# FPGA_POWER.net
KiCad netlist of a schematic drawn in Altium Designer
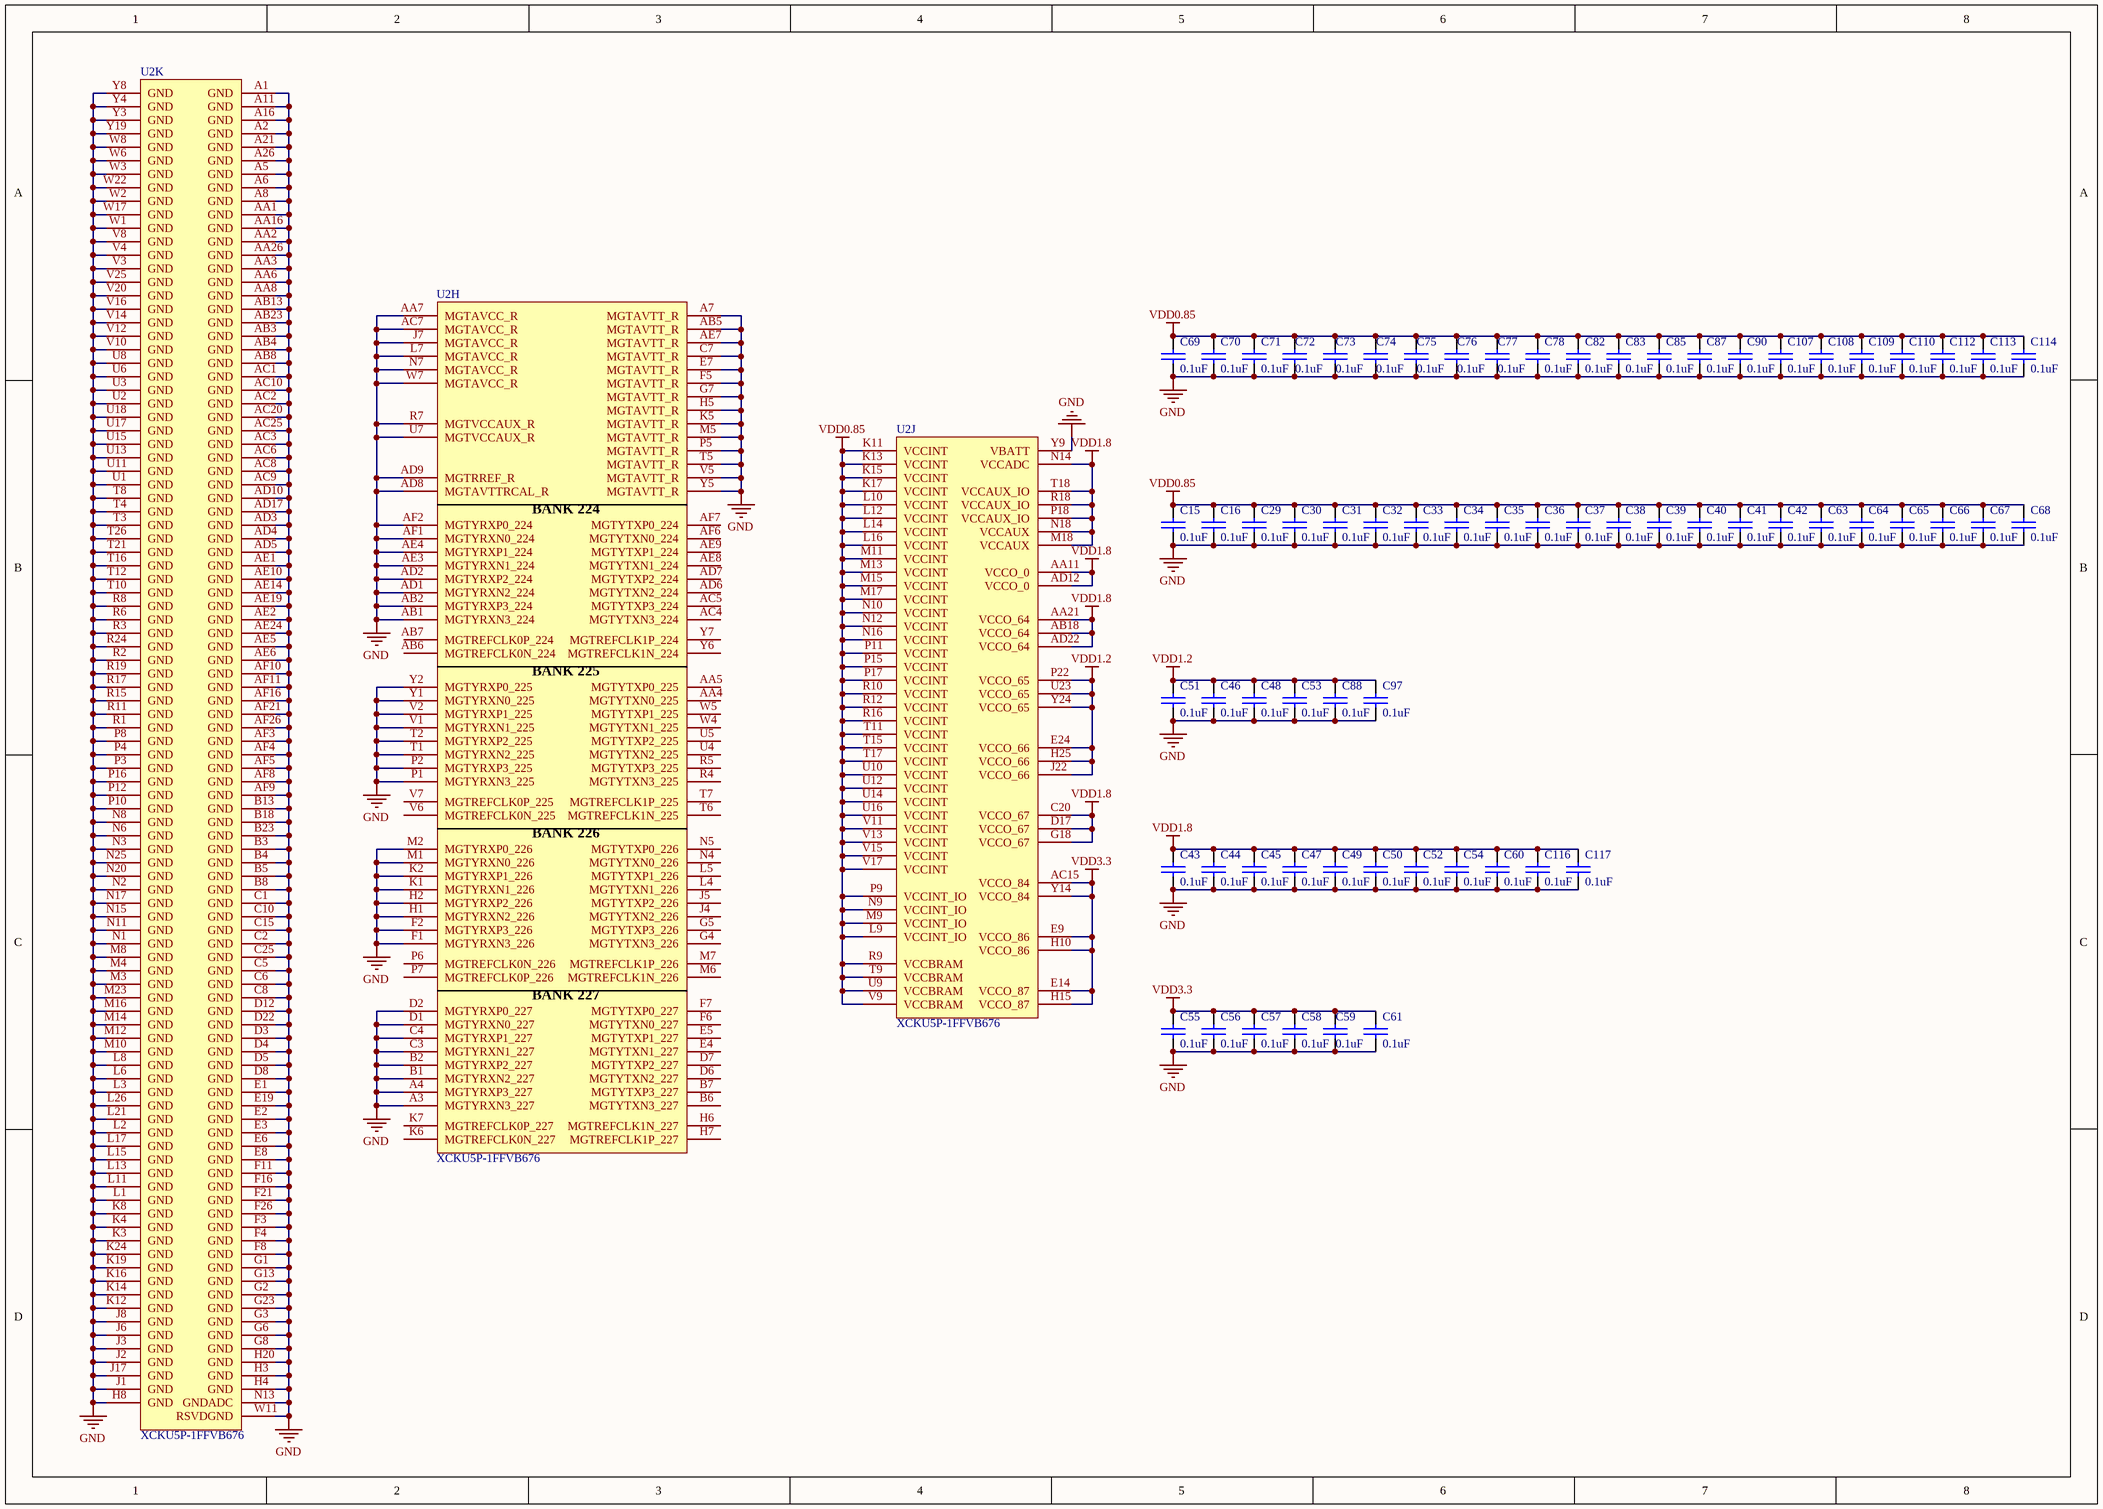
[diagram p0: FPGA POWER.SchDoc]

(export (version "E")
  (design (tool "Eeschema 10.0.6"))
  (components
    (comp (ref "C15") (value "0.1uF") (footprint "0402_C_M") (libsource (lib "Component") (part "CAP")))
    (comp (ref "C16") (value "0.1uF") (footprint "0402_C_M") (libsource (lib "Component") (part "CAP")))
    (comp (ref "C29") (value "0.1uF") (footprint "0402_C_M") (libsource (lib "Component") (part "CAP")))
    (comp (ref "C30") (value "0.1uF") (footprint "0402_C_M") (libsource (lib "Component") (part "CAP")))
    (comp (ref "C31") (value "0.1uF") (footprint "0402_C_M") (libsource (lib "Component") (part "CAP")))
    (comp (ref "C32") (value "0.1uF") (footprint "0402_C_M") (libsource (lib "Component") (part "CAP")))
    (comp (ref "C33") (value "0.1uF") (footprint "0402_C_M") (libsource (lib "Component") (part "CAP")))
    (comp (ref "C34") (value "0.1uF") (footprint "0402_C_M") (libsource (lib "Component") (part "CAP")))
    (comp (ref "C35") (value "0.1uF") (footprint "0402_C_M") (libsource (lib "Component") (part "CAP")))
    (comp (ref "C36") (value "0.1uF") (footprint "0402_C_M") (libsource (lib "Component") (part "CAP")))
    (comp (ref "C37") (value "0.1uF") (footprint "0402_C_M") (libsource (lib "Component") (part "CAP")))
    (comp (ref "C38") (value "0.1uF") (footprint "0402_C_M") (libsource (lib "Component") (part "CAP")))
    (comp (ref "C39") (value "0.1uF") (footprint "0402_C_M") (libsource (lib "Component") (part "CAP")))
    (comp (ref "C40") (value "0.1uF") (footprint "0402_C_M") (libsource (lib "Component") (part "CAP")))
    (comp (ref "C41") (value "0.1uF") (footprint "0402_C_M") (libsource (lib "Component") (part "CAP")))
    (comp (ref "C42") (value "0.1uF") (footprint "0402_C_M") (libsource (lib "Component") (part "CAP")))
    (comp (ref "C43") (value "0.1uF") (footprint "0402_C_M") (libsource (lib "Component") (part "CAP")))
    (comp (ref "C44") (value "0.1uF") (footprint "0402_C_M") (libsource (lib "Component") (part "CAP")))
    (comp (ref "C45") (value "0.1uF") (footprint "0402_C_M") (libsource (lib "Component") (part "CAP")))
    (comp (ref "C46") (value "0.1uF") (footprint "0402_C_M") (libsource (lib "Component") (part "CAP")))
    (comp (ref "C47") (value "0.1uF") (footprint "0402_C_M") (libsource (lib "Component") (part "CAP")))
    (comp (ref "C48") (value "0.1uF") (footprint "0402_C_M") (libsource (lib "Component") (part "CAP")))
    (comp (ref "C49") (value "0.1uF") (footprint "0402_C_M") (libsource (lib "Component") (part "CAP")))
    (comp (ref "C50") (value "0.1uF") (footprint "0402_C_M") (libsource (lib "Component") (part "CAP")))
    (comp (ref "C51") (value "0.1uF") (footprint "0402_C_M") (libsource (lib "Component") (part "CAP")))
    (comp (ref "C52") (value "0.1uF") (footprint "0402_C_M") (libsource (lib "Component") (part "CAP")))
    (comp (ref "C53") (value "0.1uF") (footprint "0402_C_M") (libsource (lib "Component") (part "CAP")))
    (comp (ref "C54") (value "0.1uF") (footprint "0402_c_m") (libsource (lib "My library") (part "CAP")))
    (comp (ref "C55") (value "0.1uF") (footprint "0402_C_M") (libsource (lib "Component") (part "CAP")))
    (comp (ref "C56") (value "0.1uF") (footprint "0402_C_M") (libsource (lib "Component") (part "CAP")))
    (comp (ref "C57") (value "0.1uF") (footprint "0402_C_M") (libsource (lib "Component") (part "CAP")))
    (comp (ref "C58") (value "0.1uF") (footprint "0402_C_M") (libsource (lib "Component") (part "CAP")))
    (comp (ref "C59") (value "0.1uF") (footprint "0402_C_M") (libsource (lib "Component") (part "CAP")))
    (comp (ref "C60") (value "0.1uF") (footprint "0402_C_M") (libsource (lib "Component") (part "CAP")))
    (comp (ref "C61") (value "0.1uF") (footprint "0402_C_M") (libsource (lib "Component") (part "CAP")))
    (comp (ref "C63") (value "0.1uF") (footprint "0402_C_M") (libsource (lib "Component") (part "CAP")))
    (comp (ref "C64") (value "0.1uF") (footprint "0402_C_M") (libsource (lib "Component") (part "CAP")))
    (comp (ref "C65") (value "0.1uF") (footprint "0402_C_M") (libsource (lib "Component") (part "CAP")))
    (comp (ref "C66") (value "0.1uF") (footprint "0402_C_M") (libsource (lib "Component") (part "CAP")))
    (comp (ref "C67") (value "0.1uF") (footprint "0402_C_M") (libsource (lib "Component") (part "CAP")))
    (comp (ref "C68") (value "0.1uF") (footprint "0402_C_M") (libsource (lib "Component") (part "CAP")))
    (comp (ref "C69") (value "0.1uF") (footprint "0402_C_M") (libsource (lib "Component") (part "CAP")))
    (comp (ref "C70") (value "0.1uF") (footprint "0402_C_M") (libsource (lib "Component") (part "CAP")))
    (comp (ref "C71") (value "0.1uF") (footprint "0402_C_M") (libsource (lib "Component") (part "CAP")))
    (comp (ref "C72") (value "0.1uF") (footprint "0402_C_M") (libsource (lib "Component") (part "CAP")))
    (comp (ref "C73") (value "0.1uF") (footprint "0402_C_M") (libsource (lib "Component") (part "CAP")))
    (comp (ref "C74") (value "0.1uF") (footprint "0402_C_M") (libsource (lib "Component") (part "CAP")))
    (comp (ref "C75") (value "0.1uF") (footprint "0402_C_M") (libsource (lib "Component") (part "CAP")))
    (comp (ref "C76") (value "0.1uF") (footprint "0402_C_M") (libsource (lib "Component") (part "CAP")))
    (comp (ref "C77") (value "0.1uF") (footprint "0402_C_M") (libsource (lib "Component") (part "CAP")))
    (comp (ref "C78") (value "0.1uF") (footprint "0402_C_M") (libsource (lib "Component") (part "CAP")))
    (comp (ref "C82") (value "0.1uF") (footprint "0402_C_M") (libsource (lib "Component") (part "CAP")))
    (comp (ref "C83") (value "0.1uF") (footprint "0402_C_M") (libsource (lib "Component") (part "CAP")))
    (comp (ref "C85") (value "0.1uF") (footprint "0402_C_M") (libsource (lib "Component") (part "CAP")))
    (comp (ref "C87") (value "0.1uF") (footprint "0402_C_M") (libsource (lib "Component") (part "CAP")))
    (comp (ref "C88") (value "0.1uF") (footprint "0402_C_M") (libsource (lib "Component") (part "CAP")))
    (comp (ref "C90") (value "0.1uF") (footprint "0402_C_M") (libsource (lib "Component") (part "CAP")))
    (comp (ref "C97") (value "0.1uF") (footprint "0402_C_M") (libsource (lib "Component") (part "CAP")))
    (comp (ref "C107") (value "0.1uF") (footprint "0402_C_M") (libsource (lib "Component") (part "CAP")))
    (comp (ref "C108") (value "0.1uF") (footprint "0402_C_M") (libsource (lib "Component") (part "CAP")))
    (comp (ref "C109") (value "0.1uF") (footprint "0402_C_M") (libsource (lib "Component") (part "CAP")))
    (comp (ref "C110") (value "0.1uF") (footprint "0402_C_M") (libsource (lib "Component") (part "CAP")))
    (comp (ref "C112") (value "0.1uF") (footprint "0402_C_M") (libsource (lib "Component") (part "CAP")))
    (comp (ref "C113") (value "0.1uF") (footprint "0402_C_M") (libsource (lib "Component") (part "CAP")))
    (comp (ref "C114") (value "0.1uF") (footprint "0402_C_M") (libsource (lib "Component") (part "CAP")))
    (comp (ref "C116") (value "0.1uF") (footprint "0402_C_M") (libsource (lib "Component") (part "CAP")))
    (comp (ref "C117") (value "0.1uF") (footprint "0402_C_M") (libsource (lib "Component") (part "CAP")))
    (comp (ref "U2") (value "XCKU5P-1FFVB676") (libsource (lib "XCKU5P-FFVB676") (part "XCKU5P-FFVB676")))
  )
  (nets
    (net (code "1") (name "GND") (class "Default")
      (node (ref "C107") (pin "2") (pinfunction "2_2") (pintype "passive"))
      (node (ref "C108") (pin "2") (pinfunction "2_2") (pintype "passive"))
      (node (ref "C109") (pin "2") (pinfunction "2_2") (pintype "passive"))
      (node (ref "C110") (pin "2") (pinfunction "2_2") (pintype "passive"))
      (node (ref "C112") (pin "2") (pinfunction "2_2") (pintype "passive"))
      (node (ref "C113") (pin "2") (pinfunction "2_2") (pintype "passive"))
      (node (ref "C114") (pin "2") (pinfunction "2_2") (pintype "passive"))
      (node (ref "C116") (pin "2") (pinfunction "2_2") (pintype "passive"))
      (node (ref "C117") (pin "2") (pinfunction "2_2") (pintype "passive"))
      (node (ref "C15") (pin "2") (pinfunction "2_2") (pintype "passive"))
      (node (ref "C16") (pin "2") (pinfunction "2_2") (pintype "passive"))
      (node (ref "C29") (pin "2") (pinfunction "2_2") (pintype "passive"))
      (node (ref "C30") (pin "2") (pinfunction "2_2") (pintype "passive"))
      (node (ref "C31") (pin "2") (pinfunction "2_2") (pintype "passive"))
      (node (ref "C32") (pin "2") (pinfunction "2_2") (pintype "passive"))
      (node (ref "C33") (pin "2") (pinfunction "2_2") (pintype "passive"))
      (node (ref "C34") (pin "2") (pinfunction "2_2") (pintype "passive"))
      (node (ref "C35") (pin "2") (pinfunction "2_2") (pintype "passive"))
      (node (ref "C36") (pin "2") (pinfunction "2_2") (pintype "passive"))
      (node (ref "C37") (pin "2") (pinfunction "2_2") (pintype "passive"))
      (node (ref "C38") (pin "2") (pinfunction "2_2") (pintype "passive"))
      (node (ref "C39") (pin "2") (pinfunction "2_2") (pintype "passive"))
      (node (ref "C40") (pin "2") (pinfunction "2_2") (pintype "passive"))
      (node (ref "C41") (pin "2") (pinfunction "2_2") (pintype "passive"))
      (node (ref "C42") (pin "2") (pinfunction "2_2") (pintype "passive"))
      (node (ref "C43") (pin "2") (pinfunction "2_2") (pintype "passive"))
      (node (ref "C44") (pin "2") (pinfunction "2_2") (pintype "passive"))
      (node (ref "C45") (pin "2") (pinfunction "2_2") (pintype "passive"))
      (node (ref "C46") (pin "2") (pinfunction "2_2") (pintype "passive"))
      (node (ref "C47") (pin "2") (pinfunction "2_2") (pintype "passive"))
      (node (ref "C48") (pin "2") (pinfunction "2_2") (pintype "passive"))
      (node (ref "C49") (pin "2") (pinfunction "2_2") (pintype "passive"))
      (node (ref "C50") (pin "2") (pinfunction "2_2") (pintype "passive"))
      (node (ref "C51") (pin "2") (pinfunction "2_2") (pintype "passive"))
      (node (ref "C52") (pin "2") (pinfunction "2_2") (pintype "passive"))
      (node (ref "C53") (pin "2") (pinfunction "2_2") (pintype "passive"))
      (node (ref "C54") (pin "2") (pinfunction "2_2") (pintype "passive"))
      (node (ref "C55") (pin "2") (pinfunction "2_2") (pintype "passive"))
      (node (ref "C56") (pin "2") (pinfunction "2_2") (pintype "passive"))
      (node (ref "C57") (pin "2") (pinfunction "2_2") (pintype "passive"))
      (node (ref "C58") (pin "2") (pinfunction "2_2") (pintype "passive"))
      (node (ref "C59") (pin "2") (pinfunction "2_2") (pintype "passive"))
      (node (ref "C60") (pin "2") (pinfunction "2_2") (pintype "passive"))
      (node (ref "C61") (pin "2") (pinfunction "2_2") (pintype "passive"))
      (node (ref "C63") (pin "2") (pinfunction "2_2") (pintype "passive"))
      (node (ref "C64") (pin "2") (pinfunction "2_2") (pintype "passive"))
      (node (ref "C65") (pin "2") (pinfunction "2_2") (pintype "passive"))
      (node (ref "C66") (pin "2") (pinfunction "2_2") (pintype "passive"))
      (node (ref "C67") (pin "2") (pinfunction "2_2") (pintype "passive"))
      (node (ref "C68") (pin "2") (pinfunction "2_2") (pintype "passive"))
      (node (ref "C69") (pin "2") (pinfunction "2_2") (pintype "passive"))
      (node (ref "C70") (pin "2") (pinfunction "2_2") (pintype "passive"))
      (node (ref "C71") (pin "2") (pinfunction "2_2") (pintype "passive"))
      (node (ref "C72") (pin "2") (pinfunction "2_2") (pintype "passive"))
      (node (ref "C73") (pin "2") (pinfunction "2_2") (pintype "passive"))
      (node (ref "C74") (pin "2") (pinfunction "2_2") (pintype "passive"))
      (node (ref "C75") (pin "2") (pinfunction "2_2") (pintype "passive"))
      (node (ref "C76") (pin "2") (pinfunction "2_2") (pintype "passive"))
      (node (ref "C77") (pin "2") (pinfunction "2_2") (pintype "passive"))
      (node (ref "C78") (pin "2") (pinfunction "2_2") (pintype "passive"))
      (node (ref "C82") (pin "2") (pinfunction "2_2") (pintype "passive"))
      (node (ref "C83") (pin "2") (pinfunction "2_2") (pintype "passive"))
      (node (ref "C85") (pin "2") (pinfunction "2_2") (pintype "passive"))
      (node (ref "C87") (pin "2") (pinfunction "2_2") (pintype "passive"))
      (node (ref "C88") (pin "2") (pinfunction "2_2") (pintype "passive"))
      (node (ref "C90") (pin "2") (pinfunction "2_2") (pintype "passive"))
      (node (ref "C97") (pin "2") (pinfunction "2_2") (pintype "passive"))
      (node (ref "U2") (pin "A1") (pinfunction "GND_A1") (pintype "passive"))
      (node (ref "U2") (pin "A11") (pinfunction "GND_A11") (pintype "passive"))
      (node (ref "U2") (pin "A16") (pinfunction "GND_A16") (pintype "passive"))
      (node (ref "U2") (pin "A2") (pinfunction "GND_A2") (pintype "passive"))
      (node (ref "U2") (pin "A21") (pinfunction "GND_A21") (pintype "passive"))
      (node (ref "U2") (pin "A26") (pinfunction "GND_A26") (pintype "passive"))
      (node (ref "U2") (pin "A3") (pinfunction "MGTYRXN3_227_A3") (pintype "passive"))
      (node (ref "U2") (pin "A4") (pinfunction "MGTYRXP3_227_A4") (pintype "passive"))
      (node (ref "U2") (pin "A5") (pinfunction "GND_A5") (pintype "passive"))
      (node (ref "U2") (pin "A6") (pinfunction "GND_A6") (pintype "passive"))
      (node (ref "U2") (pin "A7") (pinfunction "MGTAVTT_R_A7") (pintype "passive"))
      (node (ref "U2") (pin "A8") (pinfunction "GND_A8") (pintype "passive"))
      (node (ref "U2") (pin "AA1") (pinfunction "GND_AA1") (pintype "passive"))
      (node (ref "U2") (pin "AA16") (pinfunction "GND_AA16") (pintype "passive"))
      (node (ref "U2") (pin "AA2") (pinfunction "GND_AA2") (pintype "passive"))
      (node (ref "U2") (pin "AA26") (pinfunction "GND_AA26") (pintype "passive"))
      (node (ref "U2") (pin "AA3") (pinfunction "GND_AA3") (pintype "passive"))
      (node (ref "U2") (pin "AA6") (pinfunction "GND_AA6") (pintype "passive"))
      (node (ref "U2") (pin "AA7") (pinfunction "MGTAVCC_R_AA7") (pintype "passive"))
      (node (ref "U2") (pin "AA8") (pinfunction "GND_AA8") (pintype "passive"))
      (node (ref "U2") (pin "AB1") (pinfunction "MGTYRXN3_224_AB1") (pintype "passive"))
      (node (ref "U2") (pin "AB13") (pinfunction "GND_AB13") (pintype "passive"))
      (node (ref "U2") (pin "AB2") (pinfunction "MGTYRXP3_224_AB2") (pintype "passive"))
      (node (ref "U2") (pin "AB23") (pinfunction "GND_AB23") (pintype "passive"))
      (node (ref "U2") (pin "AB3") (pinfunction "GND_AB3") (pintype "passive"))
      (node (ref "U2") (pin "AB4") (pinfunction "GND_AB4") (pintype "passive"))
      (node (ref "U2") (pin "AB5") (pinfunction "MGTAVTT_R_AB5") (pintype "passive"))
      (node (ref "U2") (pin "AB8") (pinfunction "GND_AB8") (pintype "passive"))
      (node (ref "U2") (pin "AC1") (pinfunction "GND_AC1") (pintype "passive"))
      (node (ref "U2") (pin "AC10") (pinfunction "GND_AC10") (pintype "passive"))
      (node (ref "U2") (pin "AC2") (pinfunction "GND_AC2") (pintype "passive"))
      (node (ref "U2") (pin "AC20") (pinfunction "GND_AC20") (pintype "passive"))
      (node (ref "U2") (pin "AC25") (pinfunction "GND_AC25") (pintype "passive"))
      (node (ref "U2") (pin "AC3") (pinfunction "GND_AC3") (pintype "passive"))
      (node (ref "U2") (pin "AC6") (pinfunction "GND_AC6") (pintype "passive"))
      (node (ref "U2") (pin "AC7") (pinfunction "MGTAVCC_R_AC7") (pintype "passive"))
      (node (ref "U2") (pin "AC8") (pinfunction "GND_AC8") (pintype "passive"))
      (node (ref "U2") (pin "AC9") (pinfunction "GND_AC9") (pintype "passive"))
      (node (ref "U2") (pin "AD1") (pinfunction "MGTYRXN2_224_AD1") (pintype "passive"))
      (node (ref "U2") (pin "AD10") (pinfunction "GND_AD10") (pintype "passive"))
      (node (ref "U2") (pin "AD17") (pinfunction "GND_AD17") (pintype "passive"))
      (node (ref "U2") (pin "AD2") (pinfunction "MGTYRXP2_224_AD2") (pintype "passive"))
      (node (ref "U2") (pin "AD3") (pinfunction "GND_AD3") (pintype "passive"))
      (node (ref "U2") (pin "AD4") (pinfunction "GND_AD4") (pintype "passive"))
      (node (ref "U2") (pin "AD5") (pinfunction "GND_AD5") (pintype "passive"))
      (node (ref "U2") (pin "AD8") (pinfunction "MGTAVTTRCAL_R_AD8") (pintype "passive"))
      (node (ref "U2") (pin "AD9") (pinfunction "MGTRREF_R_AD9") (pintype "passive"))
      (node (ref "U2") (pin "AE1") (pinfunction "GND_AE1") (pintype "passive"))
      (node (ref "U2") (pin "AE10") (pinfunction "GND_AE10") (pintype "passive"))
      (node (ref "U2") (pin "AE14") (pinfunction "GND_AE14") (pintype "passive"))
      (node (ref "U2") (pin "AE19") (pinfunction "GND_AE19") (pintype "passive"))
      (node (ref "U2") (pin "AE2") (pinfunction "GND_AE2") (pintype "passive"))
      (node (ref "U2") (pin "AE24") (pinfunction "GND_AE24") (pintype "passive"))
      (node (ref "U2") (pin "AE3") (pinfunction "MGTYRXN1_224_AE3") (pintype "passive"))
      (node (ref "U2") (pin "AE4") (pinfunction "MGTYRXP1_224_AE4") (pintype "passive"))
      (node (ref "U2") (pin "AE5") (pinfunction "GND_AE5") (pintype "passive"))
      (node (ref "U2") (pin "AE6") (pinfunction "GND_AE6") (pintype "passive"))
      (node (ref "U2") (pin "AE7") (pinfunction "MGTAVTT_R_AE7") (pintype "passive"))
      (node (ref "U2") (pin "AF1") (pinfunction "MGTYRXN0_224_AF1") (pintype "passive"))
      (node (ref "U2") (pin "AF10") (pinfunction "GND_AF10") (pintype "passive"))
      (node (ref "U2") (pin "AF11") (pinfunction "GND_AF11") (pintype "passive"))
      (node (ref "U2") (pin "AF16") (pinfunction "GND_AF16") (pintype "passive"))
      (node (ref "U2") (pin "AF2") (pinfunction "MGTYRXP0_224_AF2") (pintype "passive"))
      (node (ref "U2") (pin "AF21") (pinfunction "GND_AF21") (pintype "passive"))
      (node (ref "U2") (pin "AF26") (pinfunction "GND_AF26") (pintype "passive"))
      (node (ref "U2") (pin "AF3") (pinfunction "GND_AF3") (pintype "passive"))
      (node (ref "U2") (pin "AF4") (pinfunction "GND_AF4") (pintype "passive"))
      (node (ref "U2") (pin "AF5") (pinfunction "GND_AF5") (pintype "passive"))
      (node (ref "U2") (pin "AF8") (pinfunction "GND_AF8") (pintype "passive"))
      (node (ref "U2") (pin "AF9") (pinfunction "GND_AF9") (pintype "passive"))
      (node (ref "U2") (pin "B1") (pinfunction "MGTYRXN2_227_B1") (pintype "passive"))
      (node (ref "U2") (pin "B13") (pinfunction "GND_B13") (pintype "passive"))
      (node (ref "U2") (pin "B18") (pinfunction "GND_B18") (pintype "passive"))
      (node (ref "U2") (pin "B2") (pinfunction "MGTYRXP2_227_B2") (pintype "passive"))
      (node (ref "U2") (pin "B23") (pinfunction "GND_B23") (pintype "passive"))
      (node (ref "U2") (pin "B3") (pinfunction "GND_B3") (pintype "passive"))
      (node (ref "U2") (pin "B4") (pinfunction "GND_B4") (pintype "passive"))
      (node (ref "U2") (pin "B5") (pinfunction "GND_B5") (pintype "passive"))
      (node (ref "U2") (pin "B8") (pinfunction "GND_B8") (pintype "passive"))
      (node (ref "U2") (pin "C1") (pinfunction "GND_C1") (pintype "passive"))
      (node (ref "U2") (pin "C10") (pinfunction "GND_C10") (pintype "passive"))
      (node (ref "U2") (pin "C15") (pinfunction "GND_C15") (pintype "passive"))
      (node (ref "U2") (pin "C2") (pinfunction "GND_C2") (pintype "passive"))
      (node (ref "U2") (pin "C25") (pinfunction "GND_C25") (pintype "passive"))
      (node (ref "U2") (pin "C3") (pinfunction "MGTYRXN1_227_C3") (pintype "passive"))
      (node (ref "U2") (pin "C4") (pinfunction "MGTYRXP1_227_C4") (pintype "passive"))
      (node (ref "U2") (pin "C5") (pinfunction "GND_C5") (pintype "passive"))
      (node (ref "U2") (pin "C6") (pinfunction "GND_C6") (pintype "passive"))
      (node (ref "U2") (pin "C7") (pinfunction "MGTAVTT_R_C7") (pintype "passive"))
      (node (ref "U2") (pin "C8") (pinfunction "GND_C8") (pintype "passive"))
      (node (ref "U2") (pin "D1") (pinfunction "MGTYRXN0_227_D1") (pintype "passive"))
      (node (ref "U2") (pin "D12") (pinfunction "GND_D12") (pintype "passive"))
      (node (ref "U2") (pin "D2") (pinfunction "MGTYRXP0_227_D2") (pintype "passive"))
      (node (ref "U2") (pin "D22") (pinfunction "GND_D22") (pintype "passive"))
      (node (ref "U2") (pin "D3") (pinfunction "GND_D3") (pintype "passive"))
      (node (ref "U2") (pin "D4") (pinfunction "GND_D4") (pintype "passive"))
      (node (ref "U2") (pin "D5") (pinfunction "GND_D5") (pintype "passive"))
      (node (ref "U2") (pin "D8") (pinfunction "GND_D8") (pintype "passive"))
      (node (ref "U2") (pin "E1") (pinfunction "GND_E1") (pintype "passive"))
      (node (ref "U2") (pin "E19") (pinfunction "GND_E19") (pintype "passive"))
      (node (ref "U2") (pin "E2") (pinfunction "GND_E2") (pintype "passive"))
      (node (ref "U2") (pin "E3") (pinfunction "GND_E3") (pintype "passive"))
      (node (ref "U2") (pin "E6") (pinfunction "GND_E6") (pintype "passive"))
      (node (ref "U2") (pin "E7") (pinfunction "MGTAVTT_R_E7") (pintype "passive"))
      (node (ref "U2") (pin "E8") (pinfunction "GND_E8") (pintype "passive"))
      (node (ref "U2") (pin "F1") (pinfunction "MGTYRXN3_226_F1") (pintype "passive"))
      (node (ref "U2") (pin "F11") (pinfunction "GND_F11") (pintype "passive"))
      (node (ref "U2") (pin "F16") (pinfunction "GND_F16") (pintype "passive"))
      (node (ref "U2") (pin "F2") (pinfunction "MGTYRXP3_226_F2") (pintype "passive"))
      (node (ref "U2") (pin "F21") (pinfunction "GND_F21") (pintype "passive"))
      (node (ref "U2") (pin "F26") (pinfunction "GND_F26") (pintype "passive"))
      (node (ref "U2") (pin "F3") (pinfunction "GND_F3") (pintype "passive"))
      (node (ref "U2") (pin "F4") (pinfunction "GND_F4") (pintype "passive"))
      (node (ref "U2") (pin "F5") (pinfunction "MGTAVTT_R_F5") (pintype "passive"))
      (node (ref "U2") (pin "F8") (pinfunction "GND_F8") (pintype "passive"))
      (node (ref "U2") (pin "G1") (pinfunction "GND_G1") (pintype "passive"))
      (node (ref "U2") (pin "G13") (pinfunction "GND_G13") (pintype "passive"))
      (node (ref "U2") (pin "G2") (pinfunction "GND_G2") (pintype "passive"))
      (node (ref "U2") (pin "G23") (pinfunction "GND_G23") (pintype "passive"))
      (node (ref "U2") (pin "G3") (pinfunction "GND_G3") (pintype "passive"))
      (node (ref "U2") (pin "G6") (pinfunction "GND_G6") (pintype "passive"))
      (node (ref "U2") (pin "G7") (pinfunction "MGTAVTT_R_G7") (pintype "passive"))
      (node (ref "U2") (pin "G8") (pinfunction "GND_G8") (pintype "passive"))
      (node (ref "U2") (pin "H1") (pinfunction "MGTYRXN2_226_H1") (pintype "passive"))
      (node (ref "U2") (pin "H2") (pinfunction "MGTYRXP2_226_H2") (pintype "passive"))
      (node (ref "U2") (pin "H20") (pinfunction "GND_H20") (pintype "passive"))
      (node (ref "U2") (pin "H3") (pinfunction "GND_H3") (pintype "passive"))
      (node (ref "U2") (pin "H4") (pinfunction "GND_H4") (pintype "passive"))
      (node (ref "U2") (pin "H5") (pinfunction "MGTAVTT_R_H5") (pintype "passive"))
      (node (ref "U2") (pin "H8") (pinfunction "GND_H8") (pintype "passive"))
      (node (ref "U2") (pin "J1") (pinfunction "GND_J1") (pintype "passive"))
      (node (ref "U2") (pin "J17") (pinfunction "GND_J17") (pintype "passive"))
      (node (ref "U2") (pin "J2") (pinfunction "GND_J2") (pintype "passive"))
      (node (ref "U2") (pin "J3") (pinfunction "GND_J3") (pintype "passive"))
      (node (ref "U2") (pin "J6") (pinfunction "GND_J6") (pintype "passive"))
      (node (ref "U2") (pin "J7") (pinfunction "MGTAVCC_R_J7") (pintype "passive"))
      (node (ref "U2") (pin "J8") (pinfunction "GND_J8") (pintype "passive"))
      (node (ref "U2") (pin "K1") (pinfunction "MGTYRXN1_226_K1") (pintype "passive"))
      (node (ref "U2") (pin "K12") (pinfunction "GND_K12") (pintype "passive"))
      (node (ref "U2") (pin "K14") (pinfunction "GND_K14") (pintype "passive"))
      (node (ref "U2") (pin "K16") (pinfunction "GND_K16") (pintype "passive"))
      (node (ref "U2") (pin "K19") (pinfunction "GND_K19") (pintype "passive"))
      (node (ref "U2") (pin "K2") (pinfunction "MGTYRXP1_226_K2") (pintype "passive"))
      (node (ref "U2") (pin "K24") (pinfunction "GND_K24") (pintype "passive"))
      (node (ref "U2") (pin "K3") (pinfunction "GND_K3") (pintype "passive"))
      (node (ref "U2") (pin "K4") (pinfunction "GND_K4") (pintype "passive"))
      (node (ref "U2") (pin "K5") (pinfunction "MGTAVTT_R_K5") (pintype "passive"))
      (node (ref "U2") (pin "K8") (pinfunction "GND_K8") (pintype "passive"))
      (node (ref "U2") (pin "L1") (pinfunction "GND_L1") (pintype "passive"))
      (node (ref "U2") (pin "L11") (pinfunction "GND_L11") (pintype "passive"))
      (node (ref "U2") (pin "L13") (pinfunction "GND_L13") (pintype "passive"))
      (node (ref "U2") (pin "L15") (pinfunction "GND_L15") (pintype "passive"))
      (node (ref "U2") (pin "L17") (pinfunction "GND_L17") (pintype "passive"))
      (node (ref "U2") (pin "L2") (pinfunction "GND_L2") (pintype "passive"))
      (node (ref "U2") (pin "L21") (pinfunction "GND_L21") (pintype "passive"))
      (node (ref "U2") (pin "L26") (pinfunction "GND_L26") (pintype "passive"))
      (node (ref "U2") (pin "L3") (pinfunction "GND_L3") (pintype "passive"))
      (node (ref "U2") (pin "L6") (pinfunction "GND_L6") (pintype "passive"))
      (node (ref "U2") (pin "L7") (pinfunction "MGTAVCC_R_L7") (pintype "passive"))
      (node (ref "U2") (pin "L8") (pinfunction "GND_L8") (pintype "passive"))
      (node (ref "U2") (pin "M1") (pinfunction "MGTYRXN0_226_M1") (pintype "passive"))
      (node (ref "U2") (pin "M10") (pinfunction "GND_M10") (pintype "passive"))
      (node (ref "U2") (pin "M12") (pinfunction "GND_M12") (pintype "passive"))
      (node (ref "U2") (pin "M14") (pinfunction "GND_M14") (pintype "passive"))
      (node (ref "U2") (pin "M16") (pinfunction "GND_M16") (pintype "passive"))
      (node (ref "U2") (pin "M2") (pinfunction "MGTYRXP0_226_M2") (pintype "passive"))
      (node (ref "U2") (pin "M23") (pinfunction "GND_M23") (pintype "passive"))
      (node (ref "U2") (pin "M3") (pinfunction "GND_M3") (pintype "passive"))
      (node (ref "U2") (pin "M4") (pinfunction "GND_M4") (pintype "passive"))
      (node (ref "U2") (pin "M5") (pinfunction "MGTAVTT_R_M5") (pintype "passive"))
      (node (ref "U2") (pin "M8") (pinfunction "GND_M8") (pintype "passive"))
      (node (ref "U2") (pin "N1") (pinfunction "GND_N1") (pintype "passive"))
      (node (ref "U2") (pin "N11") (pinfunction "GND_N11") (pintype "passive"))
      (node (ref "U2") (pin "N13") (pinfunction "GNDADC_N13") (pintype "passive"))
      (node (ref "U2") (pin "N15") (pinfunction "GND_N15") (pintype "passive"))
      (node (ref "U2") (pin "N17") (pinfunction "GND_N17") (pintype "passive"))
      (node (ref "U2") (pin "N2") (pinfunction "GND_N2") (pintype "passive"))
      (node (ref "U2") (pin "N20") (pinfunction "GND_N20") (pintype "passive"))
      (node (ref "U2") (pin "N25") (pinfunction "GND_N25") (pintype "passive"))
      (node (ref "U2") (pin "N3") (pinfunction "GND_N3") (pintype "passive"))
      (node (ref "U2") (pin "N6") (pinfunction "GND_N6") (pintype "passive"))
      (node (ref "U2") (pin "N7") (pinfunction "MGTAVCC_R_N7") (pintype "passive"))
      (node (ref "U2") (pin "N8") (pinfunction "GND_N8") (pintype "passive"))
      (node (ref "U2") (pin "P1") (pinfunction "MGTYRXN3_225_P1") (pintype "passive"))
      (node (ref "U2") (pin "P10") (pinfunction "GND_P10") (pintype "passive"))
      (node (ref "U2") (pin "P12") (pinfunction "GND_P12") (pintype "passive"))
      (node (ref "U2") (pin "P16") (pinfunction "GND_P16") (pintype "passive"))
      (node (ref "U2") (pin "P2") (pinfunction "MGTYRXP3_225_P2") (pintype "passive"))
      (node (ref "U2") (pin "P3") (pinfunction "GND_P3") (pintype "passive"))
      (node (ref "U2") (pin "P4") (pinfunction "GND_P4") (pintype "passive"))
      (node (ref "U2") (pin "P5") (pinfunction "MGTAVTT_R_P5") (pintype "passive"))
      (node (ref "U2") (pin "P8") (pinfunction "GND_P8") (pintype "passive"))
      (node (ref "U2") (pin "R1") (pinfunction "GND_R1") (pintype "passive"))
      (node (ref "U2") (pin "R11") (pinfunction "GND_R11") (pintype "passive"))
      (node (ref "U2") (pin "R15") (pinfunction "GND_R15") (pintype "passive"))
      (node (ref "U2") (pin "R17") (pinfunction "GND_R17") (pintype "passive"))
      (node (ref "U2") (pin "R19") (pinfunction "GND_R19") (pintype "passive"))
      (node (ref "U2") (pin "R2") (pinfunction "GND_R2") (pintype "passive"))
      (node (ref "U2") (pin "R24") (pinfunction "GND_R24") (pintype "passive"))
      (node (ref "U2") (pin "R3") (pinfunction "GND_R3") (pintype "passive"))
      (node (ref "U2") (pin "R6") (pinfunction "GND_R6") (pintype "passive"))
      (node (ref "U2") (pin "R7") (pinfunction "MGTVCCAUX_R_R7") (pintype "passive"))
      (node (ref "U2") (pin "R8") (pinfunction "GND_R8") (pintype "passive"))
      (node (ref "U2") (pin "T1") (pinfunction "MGTYRXN2_225_T1") (pintype "passive"))
      (node (ref "U2") (pin "T10") (pinfunction "GND_T10") (pintype "passive"))
      (node (ref "U2") (pin "T12") (pinfunction "GND_T12") (pintype "passive"))
      (node (ref "U2") (pin "T16") (pinfunction "GND_T16") (pintype "passive"))
      (node (ref "U2") (pin "T2") (pinfunction "MGTYRXP2_225_T2") (pintype "passive"))
      (node (ref "U2") (pin "T21") (pinfunction "GND_T21") (pintype "passive"))
      (node (ref "U2") (pin "T26") (pinfunction "GND_T26") (pintype "passive"))
      (node (ref "U2") (pin "T3") (pinfunction "GND_T3") (pintype "passive"))
      (node (ref "U2") (pin "T4") (pinfunction "GND_T4") (pintype "passive"))
      (node (ref "U2") (pin "T5") (pinfunction "MGTAVTT_R_T5") (pintype "passive"))
      (node (ref "U2") (pin "T8") (pinfunction "GND_T8") (pintype "passive"))
      (node (ref "U2") (pin "U1") (pinfunction "GND_U1") (pintype "passive"))
      (node (ref "U2") (pin "U11") (pinfunction "GND_U11") (pintype "passive"))
      (node (ref "U2") (pin "U13") (pinfunction "GND_U13") (pintype "passive"))
      (node (ref "U2") (pin "U15") (pinfunction "GND_U15") (pintype "passive"))
      (node (ref "U2") (pin "U17") (pinfunction "GND_U17") (pintype "passive"))
      (node (ref "U2") (pin "U18") (pinfunction "GND_U18") (pintype "passive"))
      (node (ref "U2") (pin "U2") (pinfunction "GND_U2") (pintype "passive"))
      (node (ref "U2") (pin "U3") (pinfunction "GND_U3") (pintype "passive"))
      (node (ref "U2") (pin "U6") (pinfunction "GND_U6") (pintype "passive"))
      (node (ref "U2") (pin "U7") (pinfunction "MGTVCCAUX_R_U7") (pintype "passive"))
      (node (ref "U2") (pin "U8") (pinfunction "GND_U8") (pintype "passive"))
      (node (ref "U2") (pin "V1") (pinfunction "MGTYRXN1_225_V1") (pintype "passive"))
      (node (ref "U2") (pin "V10") (pinfunction "GND_V10") (pintype "passive"))
      (node (ref "U2") (pin "V12") (pinfunction "GND_V12") (pintype "passive"))
      (node (ref "U2") (pin "V14") (pinfunction "GND_V14") (pintype "passive"))
      (node (ref "U2") (pin "V16") (pinfunction "GND_V16") (pintype "passive"))
      (node (ref "U2") (pin "V2") (pinfunction "MGTYRXP1_225_V2") (pintype "passive"))
      (node (ref "U2") (pin "V20") (pinfunction "GND_V20") (pintype "passive"))
      (node (ref "U2") (pin "V25") (pinfunction "GND_V25") (pintype "passive"))
      (node (ref "U2") (pin "V3") (pinfunction "GND_V3") (pintype "passive"))
      (node (ref "U2") (pin "V4") (pinfunction "GND_V4") (pintype "passive"))
      (node (ref "U2") (pin "V5") (pinfunction "MGTAVTT_R_V5") (pintype "passive"))
      (node (ref "U2") (pin "V8") (pinfunction "GND_V8") (pintype "passive"))
      (node (ref "U2") (pin "W1") (pinfunction "GND_W1") (pintype "passive"))
      (node (ref "U2") (pin "W11") (pinfunction "RSVDGND_W11") (pintype "passive"))
      (node (ref "U2") (pin "W17") (pinfunction "GND_W17") (pintype "passive"))
      (node (ref "U2") (pin "W2") (pinfunction "GND_W2") (pintype "passive"))
      (node (ref "U2") (pin "W22") (pinfunction "GND_W22") (pintype "passive"))
      (node (ref "U2") (pin "W3") (pinfunction "GND_W3") (pintype "passive"))
      (node (ref "U2") (pin "W6") (pinfunction "GND_W6") (pintype "passive"))
      (node (ref "U2") (pin "W7") (pinfunction "MGTAVCC_R_W7") (pintype "passive"))
      (node (ref "U2") (pin "W8") (pinfunction "GND_W8") (pintype "passive"))
      (node (ref "U2") (pin "Y1") (pinfunction "MGTYRXN0_225_Y1") (pintype "passive"))
      (node (ref "U2") (pin "Y19") (pinfunction "GND_Y19") (pintype "passive"))
      (node (ref "U2") (pin "Y2") (pinfunction "MGTYRXP0_225_Y2") (pintype "passive"))
      (node (ref "U2") (pin "Y3") (pinfunction "GND_Y3") (pintype "passive"))
      (node (ref "U2") (pin "Y4") (pinfunction "GND_Y4") (pintype "passive"))
      (node (ref "U2") (pin "Y5") (pinfunction "MGTAVTT_R_Y5") (pintype "passive"))
      (node (ref "U2") (pin "Y8") (pinfunction "GND_Y8") (pintype "passive"))
      (node (ref "U2") (pin "Y9") (pinfunction "VBATT_Y9") (pintype "passive"))
    )
    (net (code "2") (name "VDD0.85") (class "Default")
      (node (ref "C107") (pin "1") (pinfunction "1_1") (pintype "passive"))
      (node (ref "C108") (pin "1") (pinfunction "1_1") (pintype "passive"))
      (node (ref "C109") (pin "1") (pinfunction "1_1") (pintype "passive"))
      (node (ref "C110") (pin "1") (pinfunction "1_1") (pintype "passive"))
      (node (ref "C112") (pin "1") (pinfunction "1_1") (pintype "passive"))
      (node (ref "C113") (pin "1") (pinfunction "1_1") (pintype "passive"))
      (node (ref "C114") (pin "1") (pinfunction "1_1") (pintype "passive"))
      (node (ref "C15") (pin "1") (pinfunction "1_1") (pintype "passive"))
      (node (ref "C16") (pin "1") (pinfunction "1_1") (pintype "passive"))
      (node (ref "C29") (pin "1") (pinfunction "1_1") (pintype "passive"))
      (node (ref "C30") (pin "1") (pinfunction "1_1") (pintype "passive"))
      (node (ref "C31") (pin "1") (pinfunction "1_1") (pintype "passive"))
      (node (ref "C32") (pin "1") (pinfunction "1_1") (pintype "passive"))
      (node (ref "C33") (pin "1") (pinfunction "1_1") (pintype "passive"))
      (node (ref "C34") (pin "1") (pinfunction "1_1") (pintype "passive"))
      (node (ref "C35") (pin "1") (pinfunction "1_1") (pintype "passive"))
      (node (ref "C36") (pin "1") (pinfunction "1_1") (pintype "passive"))
      (node (ref "C37") (pin "1") (pinfunction "1_1") (pintype "passive"))
      (node (ref "C38") (pin "1") (pinfunction "1_1") (pintype "passive"))
      (node (ref "C39") (pin "1") (pinfunction "1_1") (pintype "passive"))
      (node (ref "C40") (pin "1") (pinfunction "1_1") (pintype "passive"))
      (node (ref "C41") (pin "1") (pinfunction "1_1") (pintype "passive"))
      (node (ref "C42") (pin "1") (pinfunction "1_1") (pintype "passive"))
      (node (ref "C63") (pin "1") (pinfunction "1_1") (pintype "passive"))
      (node (ref "C64") (pin "1") (pinfunction "1_1") (pintype "passive"))
      (node (ref "C65") (pin "1") (pinfunction "1_1") (pintype "passive"))
      (node (ref "C66") (pin "1") (pinfunction "1_1") (pintype "passive"))
      (node (ref "C67") (pin "1") (pinfunction "1_1") (pintype "passive"))
      (node (ref "C68") (pin "1") (pinfunction "1_1") (pintype "passive"))
      (node (ref "C69") (pin "1") (pinfunction "1_1") (pintype "passive"))
      (node (ref "C70") (pin "1") (pinfunction "1_1") (pintype "passive"))
      (node (ref "C71") (pin "1") (pinfunction "1_1") (pintype "passive"))
      (node (ref "C72") (pin "1") (pinfunction "1_1") (pintype "passive"))
      (node (ref "C73") (pin "1") (pinfunction "1_1") (pintype "passive"))
      (node (ref "C74") (pin "1") (pinfunction "1_1") (pintype "passive"))
      (node (ref "C75") (pin "1") (pinfunction "1_1") (pintype "passive"))
      (node (ref "C76") (pin "1") (pinfunction "1_1") (pintype "passive"))
      (node (ref "C77") (pin "1") (pinfunction "1_1") (pintype "passive"))
      (node (ref "C78") (pin "1") (pinfunction "1_1") (pintype "passive"))
      (node (ref "C82") (pin "1") (pinfunction "1_1") (pintype "passive"))
      (node (ref "C83") (pin "1") (pinfunction "1_1") (pintype "passive"))
      (node (ref "C85") (pin "1") (pinfunction "1_1") (pintype "passive"))
      (node (ref "C87") (pin "1") (pinfunction "1_1") (pintype "passive"))
      (node (ref "C90") (pin "1") (pinfunction "1_1") (pintype "passive"))
      (node (ref "U2") (pin "K11") (pinfunction "VCCINT_K11") (pintype "passive"))
      (node (ref "U2") (pin "K13") (pinfunction "VCCINT_K13") (pintype "passive"))
      (node (ref "U2") (pin "K15") (pinfunction "VCCINT_K15") (pintype "passive"))
      (node (ref "U2") (pin "K17") (pinfunction "VCCINT_K17") (pintype "passive"))
      (node (ref "U2") (pin "L10") (pinfunction "VCCINT_L10") (pintype "passive"))
      (node (ref "U2") (pin "L12") (pinfunction "VCCINT_L12") (pintype "passive"))
      (node (ref "U2") (pin "L14") (pinfunction "VCCINT_L14") (pintype "passive"))
      (node (ref "U2") (pin "L16") (pinfunction "VCCINT_L16") (pintype "passive"))
      (node (ref "U2") (pin "L9") (pinfunction "VCCINT_IO_L9") (pintype "passive"))
      (node (ref "U2") (pin "M11") (pinfunction "VCCINT_M11") (pintype "passive"))
      (node (ref "U2") (pin "M13") (pinfunction "VCCINT_M13") (pintype "passive"))
      (node (ref "U2") (pin "M15") (pinfunction "VCCINT_M15") (pintype "passive"))
      (node (ref "U2") (pin "M17") (pinfunction "VCCINT_M17") (pintype "passive"))
      (node (ref "U2") (pin "M9") (pinfunction "VCCINT_IO_M9") (pintype "passive"))
      (node (ref "U2") (pin "N10") (pinfunction "VCCINT_N10") (pintype "passive"))
      (node (ref "U2") (pin "N12") (pinfunction "VCCINT_N12") (pintype "passive"))
      (node (ref "U2") (pin "N16") (pinfunction "VCCINT_N16") (pintype "passive"))
      (node (ref "U2") (pin "N9") (pinfunction "VCCINT_IO_N9") (pintype "passive"))
      (node (ref "U2") (pin "P11") (pinfunction "VCCINT_P11") (pintype "passive"))
      (node (ref "U2") (pin "P15") (pinfunction "VCCINT_P15") (pintype "passive"))
      (node (ref "U2") (pin "P17") (pinfunction "VCCINT_P17") (pintype "passive"))
      (node (ref "U2") (pin "P9") (pinfunction "VCCINT_IO_P9") (pintype "passive"))
      (node (ref "U2") (pin "R10") (pinfunction "VCCINT_R10") (pintype "passive"))
      (node (ref "U2") (pin "R12") (pinfunction "VCCINT_R12") (pintype "passive"))
      (node (ref "U2") (pin "R16") (pinfunction "VCCINT_R16") (pintype "passive"))
      (node (ref "U2") (pin "R9") (pinfunction "VCCBRAM_R9") (pintype "passive"))
      (node (ref "U2") (pin "T11") (pinfunction "VCCINT_T11") (pintype "passive"))
      (node (ref "U2") (pin "T15") (pinfunction "VCCINT_T15") (pintype "passive"))
      (node (ref "U2") (pin "T17") (pinfunction "VCCINT_T17") (pintype "passive"))
      (node (ref "U2") (pin "T9") (pinfunction "VCCBRAM_T9") (pintype "passive"))
      (node (ref "U2") (pin "U10") (pinfunction "VCCINT_U10") (pintype "passive"))
      (node (ref "U2") (pin "U12") (pinfunction "VCCINT_U12") (pintype "passive"))
      (node (ref "U2") (pin "U14") (pinfunction "VCCINT_U14") (pintype "passive"))
      (node (ref "U2") (pin "U16") (pinfunction "VCCINT_U16") (pintype "passive"))
      (node (ref "U2") (pin "U9") (pinfunction "VCCBRAM_U9") (pintype "passive"))
      (node (ref "U2") (pin "V11") (pinfunction "VCCINT_V11") (pintype "passive"))
      (node (ref "U2") (pin "V13") (pinfunction "VCCINT_V13") (pintype "passive"))
      (node (ref "U2") (pin "V15") (pinfunction "VCCINT_V15") (pintype "passive"))
      (node (ref "U2") (pin "V17") (pinfunction "VCCINT_V17") (pintype "passive"))
      (node (ref "U2") (pin "V9") (pinfunction "VCCBRAM_V9") (pintype "passive"))
    )
    (net (code "3") (name "VDD1.2") (class "Default")
      (node (ref "C46") (pin "1") (pinfunction "1_1") (pintype "passive"))
      (node (ref "C48") (pin "1") (pinfunction "1_1") (pintype "passive"))
      (node (ref "C51") (pin "1") (pinfunction "1_1") (pintype "passive"))
      (node (ref "C53") (pin "1") (pinfunction "1_1") (pintype "passive"))
      (node (ref "C88") (pin "1") (pinfunction "1_1") (pintype "passive"))
      (node (ref "C97") (pin "1") (pinfunction "1_1") (pintype "passive"))
      (node (ref "U2") (pin "E24") (pinfunction "VCCO_66_E24") (pintype "passive"))
      (node (ref "U2") (pin "H25") (pinfunction "VCCO_66_H25") (pintype "passive"))
      (node (ref "U2") (pin "J22") (pinfunction "VCCO_66_J22") (pintype "passive"))
      (node (ref "U2") (pin "P22") (pinfunction "VCCO_65_P22") (pintype "passive"))
      (node (ref "U2") (pin "U23") (pinfunction "VCCO_65_U23") (pintype "passive"))
      (node (ref "U2") (pin "Y24") (pinfunction "VCCO_65_Y24") (pintype "passive"))
    )
    (net (code "4") (name "VDD1.8") (class "Default")
      (node (ref "C116") (pin "1") (pinfunction "1_1") (pintype "passive"))
      (node (ref "C117") (pin "1") (pinfunction "1_1") (pintype "passive"))
      (node (ref "C43") (pin "1") (pinfunction "1_1") (pintype "passive"))
      (node (ref "C44") (pin "1") (pinfunction "1_1") (pintype "passive"))
      (node (ref "C45") (pin "1") (pinfunction "1_1") (pintype "passive"))
      (node (ref "C47") (pin "1") (pinfunction "1_1") (pintype "passive"))
      (node (ref "C49") (pin "1") (pinfunction "1_1") (pintype "passive"))
      (node (ref "C50") (pin "1") (pinfunction "1_1") (pintype "passive"))
      (node (ref "C52") (pin "1") (pinfunction "1_1") (pintype "passive"))
      (node (ref "C54") (pin "1") (pinfunction "1_1") (pintype "passive"))
      (node (ref "C60") (pin "1") (pinfunction "1_1") (pintype "passive"))
      (node (ref "U2") (pin "AA11") (pinfunction "VCCO_0_AA11") (pintype "passive"))
      (node (ref "U2") (pin "AA21") (pinfunction "VCCO_64_AA21") (pintype "passive"))
      (node (ref "U2") (pin "AB18") (pinfunction "VCCO_64_AB18") (pintype "passive"))
      (node (ref "U2") (pin "AD12") (pinfunction "VCCO_0_AD12") (pintype "passive"))
      (node (ref "U2") (pin "AD22") (pinfunction "VCCO_64_AD22") (pintype "passive"))
      (node (ref "U2") (pin "C20") (pinfunction "VCCO_67_C20") (pintype "passive"))
      (node (ref "U2") (pin "D17") (pinfunction "VCCO_67_D17") (pintype "passive"))
      (node (ref "U2") (pin "G18") (pinfunction "VCCO_67_G18") (pintype "passive"))
      (node (ref "U2") (pin "M18") (pinfunction "VCCAUX_M18") (pintype "passive"))
      (node (ref "U2") (pin "N14") (pinfunction "VCCADC_N14") (pintype "passive"))
      (node (ref "U2") (pin "N18") (pinfunction "VCCAUX_N18") (pintype "passive"))
      (node (ref "U2") (pin "P18") (pinfunction "VCCAUX_IO_P18") (pintype "passive"))
      (node (ref "U2") (pin "R18") (pinfunction "VCCAUX_IO_R18") (pintype "passive"))
      (node (ref "U2") (pin "T18") (pinfunction "VCCAUX_IO_T18") (pintype "passive"))
    )
    (net (code "5") (name "VDD3.3") (class "Default")
      (node (ref "C55") (pin "1") (pinfunction "1_1") (pintype "passive"))
      (node (ref "C56") (pin "1") (pinfunction "1_1") (pintype "passive"))
      (node (ref "C57") (pin "1") (pinfunction "1_1") (pintype "passive"))
      (node (ref "C58") (pin "1") (pinfunction "1_1") (pintype "passive"))
      (node (ref "C59") (pin "1") (pinfunction "1_1") (pintype "passive"))
      (node (ref "C61") (pin "1") (pinfunction "1_1") (pintype "passive"))
      (node (ref "U2") (pin "AC15") (pinfunction "VCCO_84_AC15") (pintype "passive"))
      (node (ref "U2") (pin "E14") (pinfunction "VCCO_87_E14") (pintype "passive"))
      (node (ref "U2") (pin "E9") (pinfunction "VCCO_86_E9") (pintype "passive"))
      (node (ref "U2") (pin "H10") (pinfunction "VCCO_86_H10") (pintype "passive"))
      (node (ref "U2") (pin "H15") (pinfunction "VCCO_87_H15") (pintype "passive"))
      (node (ref "U2") (pin "Y14") (pinfunction "VCCO_84_Y14") (pintype "passive"))
    )
    (net (code "6") (name "unconnected-(U2H-MGTREFCLK0N_224-PadAB6)") (class "Default")
      (node (ref "U2") (pin "AB6") (pinfunction "MGTREFCLK0N_224_AB6") (pintype "passive"))
    )
    (net (code "7") (name "unconnected-(U2H-MGTREFCLK0N_225-PadV6)") (class "Default")
      (node (ref "U2") (pin "V6") (pinfunction "MGTREFCLK0N_225_V6") (pintype "passive"))
    )
    (net (code "8") (name "unconnected-(U2H-MGTREFCLK0N_226-PadP6)") (class "Default")
      (node (ref "U2") (pin "P6") (pinfunction "MGTREFCLK0N_226_P6") (pintype "passive"))
    )
    (net (code "9") (name "unconnected-(U2H-MGTREFCLK0N_227-PadK6)") (class "Default")
      (node (ref "U2") (pin "K6") (pinfunction "MGTREFCLK0N_227_K6") (pintype "passive"))
    )
    (net (code "10") (name "unconnected-(U2H-MGTREFCLK0P_224-PadAB7)") (class "Default")
      (node (ref "U2") (pin "AB7") (pinfunction "MGTREFCLK0P_224_AB7") (pintype "passive"))
    )
    (net (code "11") (name "unconnected-(U2H-MGTREFCLK0P_225-PadV7)") (class "Default")
      (node (ref "U2") (pin "V7") (pinfunction "MGTREFCLK0P_225_V7") (pintype "passive"))
    )
    (net (code "12") (name "unconnected-(U2H-MGTREFCLK0P_226-PadP7)") (class "Default")
      (node (ref "U2") (pin "P7") (pinfunction "MGTREFCLK0P_226_P7") (pintype "passive"))
    )
    (net (code "13") (name "unconnected-(U2H-MGTREFCLK0P_227-PadK7)") (class "Default")
      (node (ref "U2") (pin "K7") (pinfunction "MGTREFCLK0P_227_K7") (pintype "passive"))
    )
    (net (code "14") (name "unconnected-(U2H-MGTREFCLK1N_224-PadY6)") (class "Default")
      (node (ref "U2") (pin "Y6") (pinfunction "MGTREFCLK1N_224_Y6") (pintype "passive"))
    )
    (net (code "15") (name "unconnected-(U2H-MGTREFCLK1N_225-PadT6)") (class "Default")
      (node (ref "U2") (pin "T6") (pinfunction "MGTREFCLK1N_225_T6") (pintype "passive"))
    )
    (net (code "16") (name "unconnected-(U2H-MGTREFCLK1N_226-PadM6)") (class "Default")
      (node (ref "U2") (pin "M6") (pinfunction "MGTREFCLK1N_226_M6") (pintype "passive"))
    )
    (net (code "17") (name "unconnected-(U2H-MGTREFCLK1N_227-PadH6)") (class "Default")
      (node (ref "U2") (pin "H6") (pinfunction "MGTREFCLK1N_227_H6") (pintype "passive"))
    )
    (net (code "18") (name "unconnected-(U2H-MGTREFCLK1P_224-PadY7)") (class "Default")
      (node (ref "U2") (pin "Y7") (pinfunction "MGTREFCLK1P_224_Y7") (pintype "passive"))
    )
    (net (code "19") (name "unconnected-(U2H-MGTREFCLK1P_225-PadT7)") (class "Default")
      (node (ref "U2") (pin "T7") (pinfunction "MGTREFCLK1P_225_T7") (pintype "passive"))
    )
    (net (code "20") (name "unconnected-(U2H-MGTREFCLK1P_226-PadM7)") (class "Default")
      (node (ref "U2") (pin "M7") (pinfunction "MGTREFCLK1P_226_M7") (pintype "passive"))
    )
    (net (code "21") (name "unconnected-(U2H-MGTREFCLK1P_227-PadH7)") (class "Default")
      (node (ref "U2") (pin "H7") (pinfunction "MGTREFCLK1P_227_H7") (pintype "passive"))
    )
    (net (code "22") (name "unconnected-(U2H-MGTYTXN0_224-PadAF6)") (class "Default")
      (node (ref "U2") (pin "AF6") (pinfunction "MGTYTXN0_224_AF6") (pintype "passive"))
    )
    (net (code "23") (name "unconnected-(U2H-MGTYTXN0_225-PadAA4)") (class "Default")
      (node (ref "U2") (pin "AA4") (pinfunction "MGTYTXN0_225_AA4") (pintype "passive"))
    )
    (net (code "24") (name "unconnected-(U2H-MGTYTXN0_226-PadN4)") (class "Default")
      (node (ref "U2") (pin "N4") (pinfunction "MGTYTXN0_226_N4") (pintype "passive"))
    )
    (net (code "25") (name "unconnected-(U2H-MGTYTXN0_227-PadF6)") (class "Default")
      (node (ref "U2") (pin "F6") (pinfunction "MGTYTXN0_227_F6") (pintype "passive"))
    )
    (net (code "26") (name "unconnected-(U2H-MGTYTXN1_224-PadAE8)") (class "Default")
      (node (ref "U2") (pin "AE8") (pinfunction "MGTYTXN1_224_AE8") (pintype "passive"))
    )
    (net (code "27") (name "unconnected-(U2H-MGTYTXN1_225-PadW4)") (class "Default")
      (node (ref "U2") (pin "W4") (pinfunction "MGTYTXN1_225_W4") (pintype "passive"))
    )
    (net (code "28") (name "unconnected-(U2H-MGTYTXN1_226-PadL4)") (class "Default")
      (node (ref "U2") (pin "L4") (pinfunction "MGTYTXN1_226_L4") (pintype "passive"))
    )
    (net (code "29") (name "unconnected-(U2H-MGTYTXN1_227-PadE4)") (class "Default")
      (node (ref "U2") (pin "E4") (pinfunction "MGTYTXN1_227_E4") (pintype "passive"))
    )
    (net (code "30") (name "unconnected-(U2H-MGTYTXN2_224-PadAD6)") (class "Default")
      (node (ref "U2") (pin "AD6") (pinfunction "MGTYTXN2_224_AD6") (pintype "passive"))
    )
    (net (code "31") (name "unconnected-(U2H-MGTYTXN2_225-PadU4)") (class "Default")
      (node (ref "U2") (pin "U4") (pinfunction "MGTYTXN2_225_U4") (pintype "passive"))
    )
    (net (code "32") (name "unconnected-(U2H-MGTYTXN2_226-PadJ4)") (class "Default")
      (node (ref "U2") (pin "J4") (pinfunction "MGTYTXN2_226_J4") (pintype "passive"))
    )
    (net (code "33") (name "unconnected-(U2H-MGTYTXN2_227-PadD6)") (class "Default")
      (node (ref "U2") (pin "D6") (pinfunction "MGTYTXN2_227_D6") (pintype "passive"))
    )
    (net (code "34") (name "unconnected-(U2H-MGTYTXN3_224-PadAC4)") (class "Default")
      (node (ref "U2") (pin "AC4") (pinfunction "MGTYTXN3_224_AC4") (pintype "passive"))
    )
    (net (code "35") (name "unconnected-(U2H-MGTYTXN3_225-PadR4)") (class "Default")
      (node (ref "U2") (pin "R4") (pinfunction "MGTYTXN3_225_R4") (pintype "passive"))
    )
    (net (code "36") (name "unconnected-(U2H-MGTYTXN3_226-PadG4)") (class "Default")
      (node (ref "U2") (pin "G4") (pinfunction "MGTYTXN3_226_G4") (pintype "passive"))
    )
    (net (code "37") (name "unconnected-(U2H-MGTYTXN3_227-PadB6)") (class "Default")
      (node (ref "U2") (pin "B6") (pinfunction "MGTYTXN3_227_B6") (pintype "passive"))
    )
    (net (code "38") (name "unconnected-(U2H-MGTYTXP0_224-PadAF7)") (class "Default")
      (node (ref "U2") (pin "AF7") (pinfunction "MGTYTXP0_224_AF7") (pintype "passive"))
    )
    (net (code "39") (name "unconnected-(U2H-MGTYTXP0_225-PadAA5)") (class "Default")
      (node (ref "U2") (pin "AA5") (pinfunction "MGTYTXP0_225_AA5") (pintype "passive"))
    )
    (net (code "40") (name "unconnected-(U2H-MGTYTXP0_226-PadN5)") (class "Default")
      (node (ref "U2") (pin "N5") (pinfunction "MGTYTXP0_226_N5") (pintype "passive"))
    )
    (net (code "41") (name "unconnected-(U2H-MGTYTXP0_227-PadF7)") (class "Default")
      (node (ref "U2") (pin "F7") (pinfunction "MGTYTXP0_227_F7") (pintype "passive"))
    )
    (net (code "42") (name "unconnected-(U2H-MGTYTXP1_224-PadAE9)") (class "Default")
      (node (ref "U2") (pin "AE9") (pinfunction "MGTYTXP1_224_AE9") (pintype "passive"))
    )
    (net (code "43") (name "unconnected-(U2H-MGTYTXP1_225-PadW5)") (class "Default")
      (node (ref "U2") (pin "W5") (pinfunction "MGTYTXP1_225_W5") (pintype "passive"))
    )
    (net (code "44") (name "unconnected-(U2H-MGTYTXP1_226-PadL5)") (class "Default")
      (node (ref "U2") (pin "L5") (pinfunction "MGTYTXP1_226_L5") (pintype "passive"))
    )
    (net (code "45") (name "unconnected-(U2H-MGTYTXP1_227-PadE5)") (class "Default")
      (node (ref "U2") (pin "E5") (pinfunction "MGTYTXP1_227_E5") (pintype "passive"))
    )
    (net (code "46") (name "unconnected-(U2H-MGTYTXP2_224-PadAD7)") (class "Default")
      (node (ref "U2") (pin "AD7") (pinfunction "MGTYTXP2_224_AD7") (pintype "passive"))
    )
    (net (code "47") (name "unconnected-(U2H-MGTYTXP2_225-PadU5)") (class "Default")
      (node (ref "U2") (pin "U5") (pinfunction "MGTYTXP2_225_U5") (pintype "passive"))
    )
    (net (code "48") (name "unconnected-(U2H-MGTYTXP2_226-PadJ5)") (class "Default")
      (node (ref "U2") (pin "J5") (pinfunction "MGTYTXP2_226_J5") (pintype "passive"))
    )
    (net (code "49") (name "unconnected-(U2H-MGTYTXP2_227-PadD7)") (class "Default")
      (node (ref "U2") (pin "D7") (pinfunction "MGTYTXP2_227_D7") (pintype "passive"))
    )
    (net (code "50") (name "unconnected-(U2H-MGTYTXP3_224-PadAC5)") (class "Default")
      (node (ref "U2") (pin "AC5") (pinfunction "MGTYTXP3_224_AC5") (pintype "passive"))
    )
    (net (code "51") (name "unconnected-(U2H-MGTYTXP3_225-PadR5)") (class "Default")
      (node (ref "U2") (pin "R5") (pinfunction "MGTYTXP3_225_R5") (pintype "passive"))
    )
    (net (code "52") (name "unconnected-(U2H-MGTYTXP3_226-PadG5)") (class "Default")
      (node (ref "U2") (pin "G5") (pinfunction "MGTYTXP3_226_G5") (pintype "passive"))
    )
    (net (code "53") (name "unconnected-(U2H-MGTYTXP3_227-PadB7)") (class "Default")
      (node (ref "U2") (pin "B7") (pinfunction "MGTYTXP3_227_B7") (pintype "passive"))
    )
  )
)
